# Amazing-All-Band-Receiver-alt.net
KiCad netlist of a schematic drawn in EAGLE
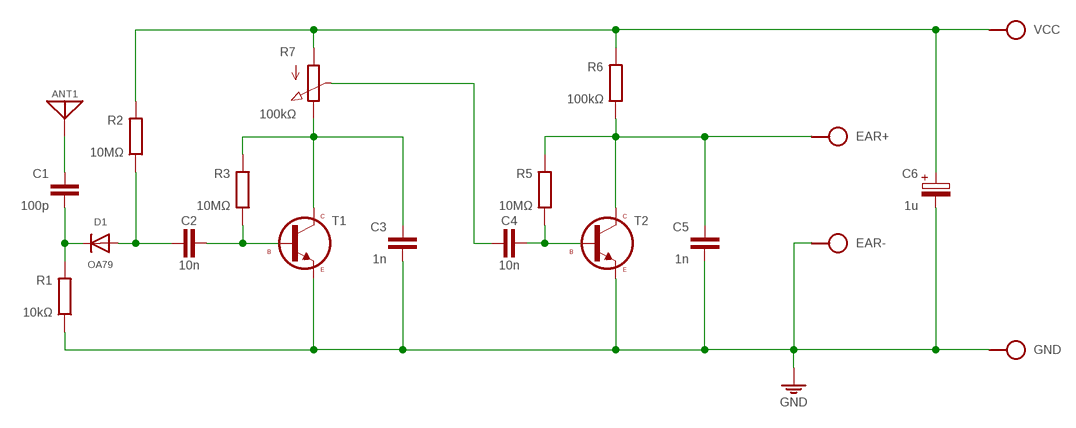
[diagram p0: schematic, sheet 1]

(export (version "E")
  (design (tool "Eeschema 10.0.6"))
  (components
    (comp (ref "ANT1")
      (value "ANT")
      (footprint "eagle-import:SPAD")
      (libsource (lib "eagle-import") (part "ANT"))
    )
    (comp (ref "C1")
      (value "100p")
      (footprint "eagle-import:C050-020X036_V")
      (libsource (lib "eagle-import") (part "C050-020X036/V"))
    )
    (comp (ref "C2")
      (value "10n")
      (footprint "eagle-import:C050-020X036")
      (libsource (lib "eagle-import") (part "C050-020X036"))
    )
    (comp (ref "C3")
      (value "1n")
      (footprint "eagle-import:C050-020X036")
      (libsource (lib "eagle-import") (part "C050-020X036"))
    )
    (comp (ref "C4")
      (value "10n")
      (footprint "eagle-import:C050-020X036")
      (libsource (lib "eagle-import") (part "C050-020X036"))
    )
    (comp (ref "C5")
      (value "1n")
      (footprint "eagle-import:C050-020X036")
      (libsource (lib "eagle-import") (part "C050-020X036"))
    )
    (comp (ref "C6")
      (value "1u")
      (footprint "eagle-import:E2,5-3")
      (libsource (lib "eagle-import") (part "CPOLE2,5-3"))
    )
    (comp (ref "D1")
      (value "OA79")
      (footprint "eagle-import:DO34-7V")
      (libsource (lib "eagle-import") (part "1N414834-7V"))
    )
    (comp (ref "EAR+")
      (value "SPAD")
      (footprint "eagle-import:SPAD")
      (libsource (lib "eagle-import") (part "SPAD"))
    )
    (comp (ref "EAR-")
      (value "SPAD")
      (footprint "eagle-import:SPAD")
      (libsource (lib "eagle-import") (part "SPAD"))
    )
    (comp (ref "GND")
      (value "SPAD")
      (footprint "eagle-import:SPAD")
      (libsource (lib "eagle-import") (part "SPAD"))
    )
    (comp (ref "R1")
      (value "10kΩ")
      (footprint "eagle-import:0202_7-V")
      (libsource (lib "eagle-import") (part "R0202/7-V"))
    )
    (comp (ref "R2")
      (value "10MΩ")
      (footprint "eagle-import:0202_7")
      (libsource (lib "eagle-import") (part "R0202/7"))
    )
    (comp (ref "R3")
      (value "10MΩ")
      (footprint "eagle-import:0202_7-V")
      (libsource (lib "eagle-import") (part "R0202/7-V"))
    )
    (comp (ref "R5")
      (value "10MΩ")
      (footprint "eagle-import:0202_7-V")
      (libsource (lib "eagle-import") (part "R0202/7-V"))
    )
    (comp (ref "R6")
      (value "100kΩ")
      (footprint "eagle-import:0202_7-V")
      (libsource (lib "eagle-import") (part "R0202/7-V"))
    )
    (comp (ref "R7")
      (value "100kΩ")
      (footprint "eagle-import:POT")
      (libsource (lib "eagle-import") (part "POT"))
    )
    (comp (ref "T1")
      (value "BC547-TO92-CBE")
      (footprint "eagle-import:TO92-CBE")
      (libsource (lib "eagle-import") (part "BC547-TO92-CBE"))
    )
    (comp (ref "T2")
      (value "BC547")
      (footprint "eagle-import:TO92")
      (libsource (lib "eagle-import") (part "BC547"))
    )
    (comp (ref "VCC")
      (value "SPAD")
      (footprint "eagle-import:SPAD")
      (libsource (lib "eagle-import") (part "SPAD"))
    )
  )
  (nets
    (net (code "1") (name "GND") (class "Default")
      (node (ref "C3") (pin "2") (pinfunction "2_2") (pintype "passive"))
      (node (ref "C5") (pin "2") (pinfunction "2_2") (pintype "passive"))
      (node (ref "C6") (pin "-") (pinfunction "-_-") (pintype "passive"))
      (node (ref "EAR-") (pin "1") (pinfunction "P$1_1") (pintype "bidirectional"))
      (node (ref "GND") (pin "1") (pinfunction "P$1_1") (pintype "bidirectional"))
      (node (ref "R1") (pin "1") (pinfunction "1_1") (pintype "passive"))
      (node (ref "T1") (pin "3") (pinfunction "E_3") (pintype "passive"))
      (node (ref "T2") (pin "3") (pinfunction "E_3") (pintype "passive"))
    )
    (net (code "2") (name "Net-(ANT1-Pad1)") (class "Default")
      (node (ref "ANT1") (pin "1") (pinfunction "1_1") (pintype "output"))
      (node (ref "C1") (pin "1") (pinfunction "1_1") (pintype "passive"))
    )
    (net (code "3") (name "Net-(C1-Pad2)") (class "Default")
      (node (ref "C1") (pin "2") (pinfunction "2_2") (pintype "passive"))
      (node (ref "D1") (pin "C") (pinfunction "C_C") (pintype "passive"))
      (node (ref "R1") (pin "2") (pinfunction "2_2") (pintype "passive"))
    )
    (net (code "4") (name "Net-(C2-Pad2)") (class "Default")
      (node (ref "C2") (pin "2") (pinfunction "2_2") (pintype "passive"))
      (node (ref "D1") (pin "A") (pinfunction "A_A") (pintype "passive"))
      (node (ref "R2") (pin "1") (pinfunction "1_1") (pintype "passive"))
    )
    (net (code "5") (name "Net-(EAR+-P$1)") (class "Default")
      (node (ref "C5") (pin "1") (pinfunction "1_1") (pintype "passive"))
      (node (ref "EAR+") (pin "1") (pinfunction "P$1_1") (pintype "bidirectional"))
      (node (ref "R5") (pin "2") (pinfunction "2_2") (pintype "passive"))
      (node (ref "R6") (pin "1") (pinfunction "1_1") (pintype "passive"))
      (node (ref "T2") (pin "1") (pinfunction "C_1") (pintype "passive"))
    )
    (net (code "6") (name "Net-(R7-A)") (class "Default")
      (node (ref "C6") (pin "+") (pinfunction "+_+") (pintype "passive"))
      (node (ref "R2") (pin "2") (pinfunction "2_2") (pintype "passive"))
      (node (ref "R6") (pin "2") (pinfunction "2_2") (pintype "passive"))
      (node (ref "R7") (pin "1") (pinfunction "A_1") (pintype "passive"))
      (node (ref "VCC") (pin "1") (pinfunction "P$1_1") (pintype "bidirectional"))
    )
    (net (code "7") (name "Net-(R7-E)") (class "Default")
      (node (ref "C3") (pin "1") (pinfunction "1_1") (pintype "passive"))
      (node (ref "R3") (pin "2") (pinfunction "2_2") (pintype "passive"))
      (node (ref "R7") (pin "3") (pinfunction "E_3") (pintype "passive"))
      (node (ref "T1") (pin "1") (pinfunction "C_1") (pintype "passive"))
    )
    (net (code "8") (name "Net-(R7-S)") (class "Default")
      (node (ref "C4") (pin "2") (pinfunction "2_2") (pintype "passive"))
      (node (ref "R7") (pin "2") (pinfunction "S_2") (pintype "passive"))
    )
    (net (code "9") (name "Net-(T1-B)") (class "Default")
      (node (ref "C2") (pin "1") (pinfunction "1_1") (pintype "passive"))
      (node (ref "R3") (pin "1") (pinfunction "1_1") (pintype "passive"))
      (node (ref "T1") (pin "2") (pinfunction "B_2") (pintype "passive"))
    )
    (net (code "10") (name "Net-(T2-B)") (class "Default")
      (node (ref "C4") (pin "1") (pinfunction "1_1") (pintype "passive"))
      (node (ref "R5") (pin "1") (pinfunction "1_1") (pintype "passive"))
      (node (ref "T2") (pin "2") (pinfunction "B_2") (pintype "passive"))
    )
  )
)
